# Ambiente_inferior.net
KiCad netlist of a schematic drawn in EAGLE
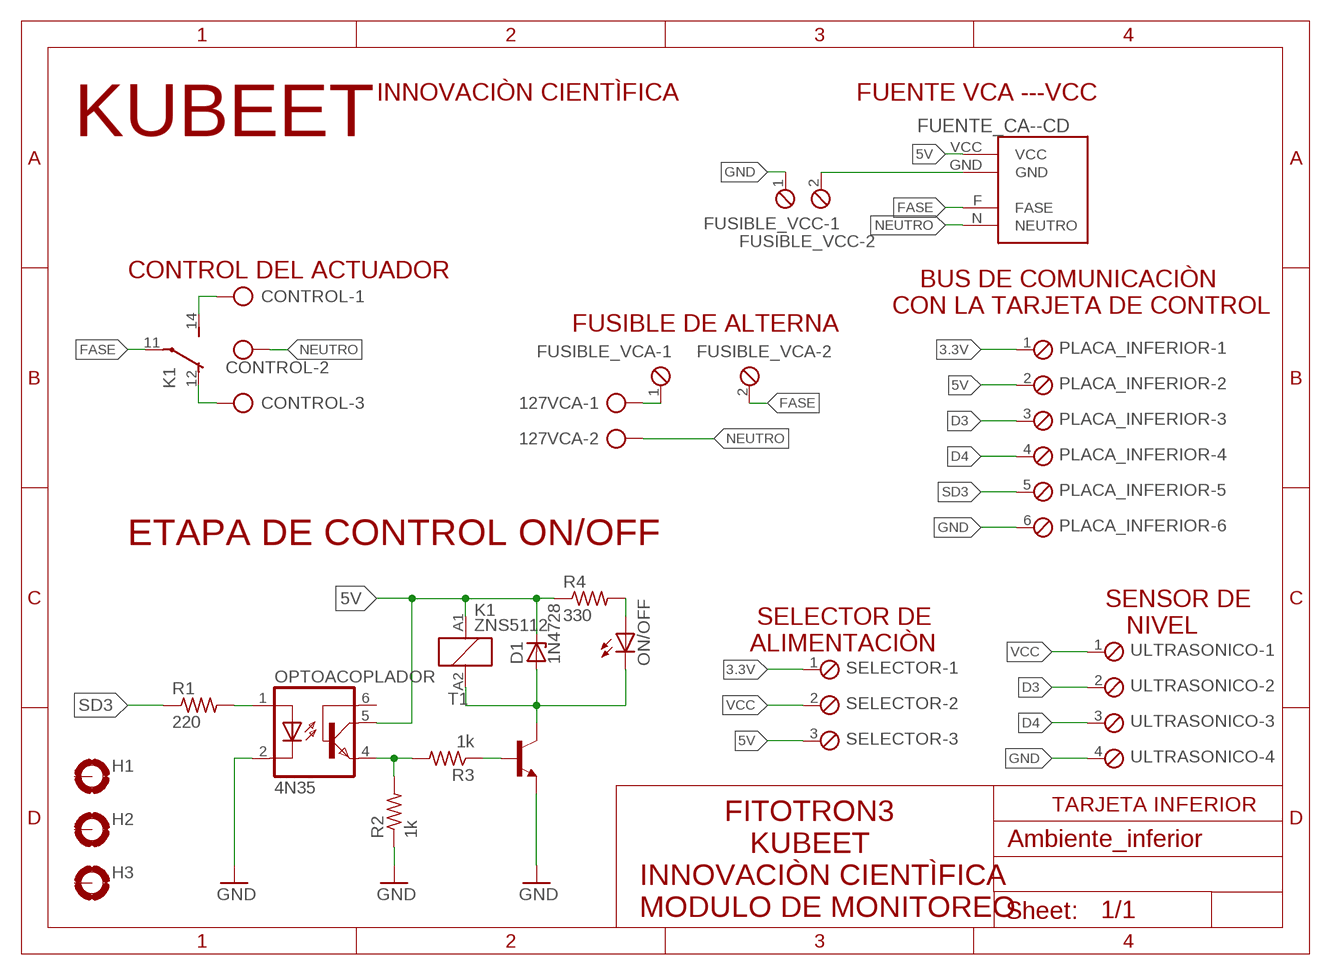
[diagram p0: schematic, sheet 1]

(export (version "E")
  (design (tool "Eeschema 10.0.6"))
  (components
    (comp (ref "127VCA")
      (value "AK300/2")
      (footprint "eagle-import:AK300_2")
      (libsource (lib "eagle-import") (part "AK300/2"))
    )
    (comp (ref "CONTROL")
      (value "AK300/3")
      (footprint "eagle-import:AK300_3")
      (libsource (lib "eagle-import") (part "AK300/3"))
    )
    (comp (ref "D1")
      (value "1N4728")
      (footprint "eagle-import:DO41Z10")
      (libsource (lib "eagle-import") (part "1N4728"))
    )
    (comp (ref "FUENTE_CA--CD")
      (value "MINI-FUENTE")
      (footprint "eagle-import:MINI-FUENTE")
      (libsource (lib "eagle-import") (part "MINI-FUENTE"))
    )
    (comp (ref "FUSIBLE_VCA")
      (value "MPT2")
      (footprint "eagle-import:2POL254")
      (libsource (lib "eagle-import") (part "MPT2"))
    )
    (comp (ref "FUSIBLE_VCC")
      (value "MPT2")
      (footprint "eagle-import:2POL254")
      (libsource (lib "eagle-import") (part "MPT2"))
    )
    (comp (ref "H1")
      (value "MOUNT-PAD-ROUND3.6")
      (footprint "eagle-import:3,6-PAD")
      (libsource (lib "eagle-import") (part "MOUNT-PAD-ROUND3.6"))
    )
    (comp (ref "H2")
      (value "MOUNT-PAD-ROUND3.6")
      (footprint "eagle-import:3,6-PAD")
      (libsource (lib "eagle-import") (part "MOUNT-PAD-ROUND3.6"))
    )
    (comp (ref "H3")
      (value "MOUNT-PAD-ROUND3.6")
      (footprint "eagle-import:3,6-PAD")
      (libsource (lib "eagle-import") (part "MOUNT-PAD-ROUND3.6"))
    )
    (comp (ref "K1")
      (value "ZNS5112")
      (footprint "eagle-import:ZN5")
      (libsource (lib "eagle-import") (part "ZNS5112"))
    )
    (comp (ref "ON/OFF")
      (value "LED5MM")
      (footprint "eagle-import:LED5MM")
      (libsource (lib "eagle-import") (part "LED5MM"))
    )
    (comp (ref "OPTOACOPLADOR")
      (value "4N35")
      (footprint "eagle-import:DIL06")
      (fields (field (name "MPN") "4N25-M"))
      (libsource (lib "eagle-import") (part "4N?M25"))
    )
    (comp (ref "PLACA_INFERIOR")
      (value "MPT6")
      (footprint "eagle-import:6POL254")
      (libsource (lib "eagle-import") (part "MPT6"))
    )
    (comp (ref "R1")
      (value "220")
      (footprint "eagle-import:0207_7")
      (libsource (lib "eagle-import") (part "R-US_0207/7"))
    )
    (comp (ref "R2")
      (value "1k")
      (footprint "eagle-import:0207_7")
      (libsource (lib "eagle-import") (part "R-US_0207/7"))
    )
    (comp (ref "R3")
      (value "1k")
      (footprint "eagle-import:0207_7")
      (libsource (lib "eagle-import") (part "R-US_0207/7"))
    )
    (comp (ref "R4")
      (value "330")
      (footprint "eagle-import:0207_7")
      (libsource (lib "eagle-import") (part "R-US_0207/7"))
    )
    (comp (ref "SELECTOR")
      (value "MPT3")
      (footprint "eagle-import:3POL254")
      (libsource (lib "eagle-import") (part "MPT3"))
    )
    (comp (ref "T1")
      (value "2N2222-NPN-TO92-EBC")
      (footprint "eagle-import:TO92-EBC")
      (libsource (lib "eagle-import") (part "-NPN-TO92-EBC2N2222"))
    )
    (comp (ref "ULTRASONICO")
      (value "MPT4")
      (footprint "eagle-import:4POL254")
      (libsource (lib "eagle-import") (part "MPT4"))
    )
  )
  (nets
    (net (code "1") (name "3.3V") (class "Default")
      (node (ref "PLACA_INFERIOR") (pin "1") (pinfunction "1_1") (pintype "passive"))
      (node (ref "SELECTOR") (pin "1") (pinfunction "1_1") (pintype "passive"))
    )
    (net (code "2") (name "5V") (class "Default")
      (node (ref "D1") (pin "C") (pinfunction "C_C") (pintype "passive"))
      (node (ref "FUENTE_CA--CD") (pin "VCC") (pinfunction "VCC_VCC") (pintype "bidirectional"))
      (node (ref "K1") (pin "A1") (pinfunction "1_A1") (pintype "passive"))
      (node (ref "OPTOACOPLADOR") (pin "5") (pinfunction "COL_5") (pintype "passive"))
      (node (ref "PLACA_INFERIOR") (pin "2") (pinfunction "1_2") (pintype "passive"))
      (node (ref "R4") (pin "1") (pinfunction "1_1") (pintype "passive"))
      (node (ref "SELECTOR") (pin "3") (pinfunction "1_3") (pintype "passive"))
    )
    (net (code "3") (name "D3") (class "Default")
      (node (ref "PLACA_INFERIOR") (pin "3") (pinfunction "1_3") (pintype "passive"))
      (node (ref "ULTRASONICO") (pin "2") (pinfunction "1_2") (pintype "passive"))
    )
    (net (code "4") (name "D4") (class "Default")
      (node (ref "PLACA_INFERIOR") (pin "4") (pinfunction "1_4") (pintype "passive"))
      (node (ref "ULTRASONICO") (pin "3") (pinfunction "1_3") (pintype "passive"))
    )
    (net (code "5") (name "FASE") (class "Default")
      (node (ref "FUENTE_CA--CD") (pin "F") (pinfunction "FASE_F") (pintype "bidirectional"))
      (node (ref "FUSIBLE_VCA") (pin "2") (pinfunction "1_2") (pintype "passive"))
      (node (ref "K1") (pin "11") (pinfunction "P_11") (pintype "passive"))
    )
    (net (code "6") (name "GND") (class "Default")
      (node (ref "FUSIBLE_VCC") (pin "1") (pinfunction "1_1") (pintype "passive"))
      (node (ref "OPTOACOPLADOR") (pin "2") (pinfunction "C_2") (pintype "passive"))
      (node (ref "PLACA_INFERIOR") (pin "6") (pinfunction "1_6") (pintype "passive"))
      (node (ref "R2") (pin "1") (pinfunction "1_1") (pintype "passive"))
      (node (ref "T1") (pin "E") (pinfunction "E_E") (pintype "passive"))
      (node (ref "ULTRASONICO") (pin "4") (pinfunction "1_4") (pintype "passive"))
    )
    (net (code "7") (name "NEUTRO") (class "Default")
      (node (ref "127VCA") (pin "2") (pinfunction "KL_2") (pintype "passive"))
      (node (ref "CONTROL") (pin "2") (pinfunction "KL_2") (pintype "passive"))
      (node (ref "FUENTE_CA--CD") (pin "N") (pinfunction "NEUTRO_N") (pintype "bidirectional"))
    )
    (net (code "8") (name "Net-(127VCAA-KL)") (class "Default")
      (node (ref "127VCA") (pin "1") (pinfunction "KL_1") (pintype "passive"))
      (node (ref "FUSIBLE_VCA") (pin "1") (pinfunction "1_1") (pintype "passive"))
    )
    (net (code "9") (name "Net-(CONTROLA-KL)") (class "Default")
      (node (ref "CONTROL") (pin "1") (pinfunction "KL_1") (pintype "passive"))
      (node (ref "K1") (pin "14") (pinfunction "S_14") (pintype "passive"))
    )
    (net (code "10") (name "Net-(CONTROLC-KL)") (class "Default")
      (node (ref "CONTROL") (pin "3") (pinfunction "KL_3") (pintype "passive"))
      (node (ref "K1") (pin "12") (pinfunction "O_12") (pintype "passive"))
    )
    (net (code "11") (name "Net-(FUSIBLE_VCCB-1)") (class "Default")
      (node (ref "FUENTE_CA--CD") (pin "GND") (pinfunction "GND_GND") (pintype "bidirectional"))
      (node (ref "FUSIBLE_VCC") (pin "2") (pinfunction "1_2") (pintype "passive"))
    )
    (net (code "12") (name "Net-(K1A-2)") (class "Default")
      (node (ref "D1") (pin "A") (pinfunction "A_A") (pintype "passive"))
      (node (ref "K1") (pin "A2") (pinfunction "2_A2") (pintype "passive"))
      (node (ref "ON/OFF") (pin "K") (pinfunction "C_K") (pintype "passive"))
      (node (ref "T1") (pin "C") (pinfunction "C_C") (pintype "passive"))
    )
    (net (code "13") (name "Net-(ON/OFF-PadA)") (class "Default")
      (node (ref "ON/OFF") (pin "A") (pinfunction "A_A") (pintype "passive"))
      (node (ref "R4") (pin "2") (pinfunction "2_2") (pintype "passive"))
    )
    (net (code "14") (name "Net-(OPTOACOPLADOR-A)") (class "Default")
      (node (ref "OPTOACOPLADOR") (pin "1") (pinfunction "A_1") (pintype "passive"))
      (node (ref "R1") (pin "2") (pinfunction "2_2") (pintype "passive"))
    )
    (net (code "15") (name "Net-(OPTOACOPLADOR-EMI)") (class "Default")
      (node (ref "OPTOACOPLADOR") (pin "4") (pinfunction "EMI_4") (pintype "passive"))
      (node (ref "R2") (pin "2") (pinfunction "2_2") (pintype "passive"))
      (node (ref "R3") (pin "2") (pinfunction "2_2") (pintype "passive"))
    )
    (net (code "16") (name "Net-(R3-Pad1)") (class "Default")
      (node (ref "R3") (pin "1") (pinfunction "1_1") (pintype "passive"))
      (node (ref "T1") (pin "B") (pinfunction "B_B") (pintype "passive"))
    )
    (net (code "17") (name "SD3") (class "Default")
      (node (ref "PLACA_INFERIOR") (pin "5") (pinfunction "1_5") (pintype "passive"))
      (node (ref "R1") (pin "1") (pinfunction "1_1") (pintype "passive"))
    )
    (net (code "18") (name "VCC") (class "Default")
      (node (ref "SELECTOR") (pin "2") (pinfunction "1_2") (pintype "passive"))
      (node (ref "ULTRASONICO") (pin "1") (pinfunction "1_1") (pintype "passive"))
    )
    (net (code "19") (name "unconnected-(H1-MOUNT-PadB3,6)") (class "Default")
      (node (ref "H1") (pin "B3,6") (pinfunction "MOUNT_B3,6") (pintype "passive"))
    )
    (net (code "20") (name "unconnected-(H2-MOUNT-PadB3,6)") (class "Default")
      (node (ref "H2") (pin "B3,6") (pinfunction "MOUNT_B3,6") (pintype "passive"))
    )
    (net (code "21") (name "unconnected-(H3-MOUNT-PadB3,6)") (class "Default")
      (node (ref "H3") (pin "B3,6") (pinfunction "MOUNT_B3,6") (pintype "passive"))
    )
    (net (code "22") (name "unconnected-(OPTOACOPLADOR-BAS-Pad6)") (class "Default")
      (node (ref "OPTOACOPLADOR") (pin "6") (pinfunction "BAS_6") (pintype "passive"))
    )
  )
)
